# AQS.net
KiCad netlist of a schematic drawn in EAGLE
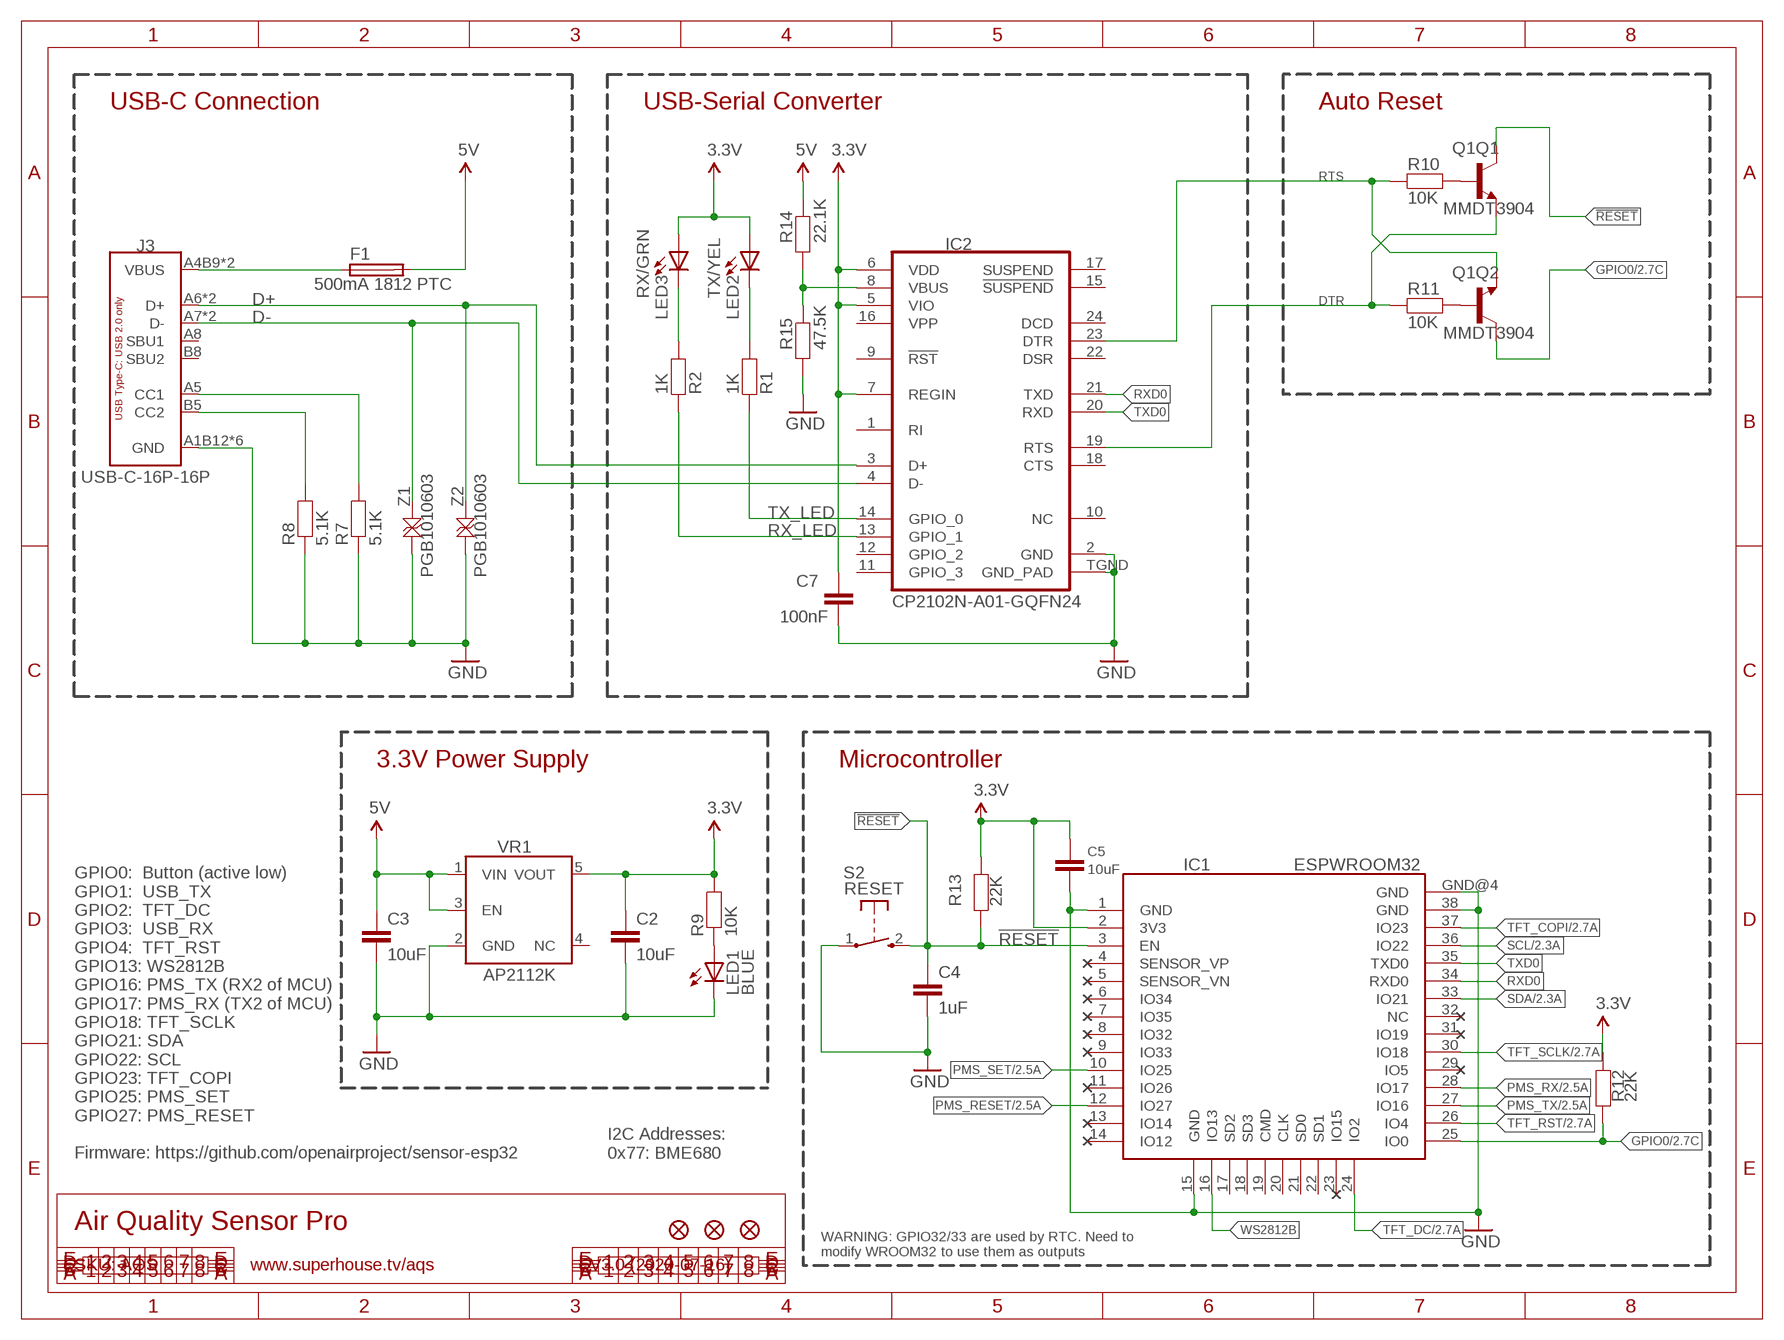
[diagram p0: schematic, sheet 1]
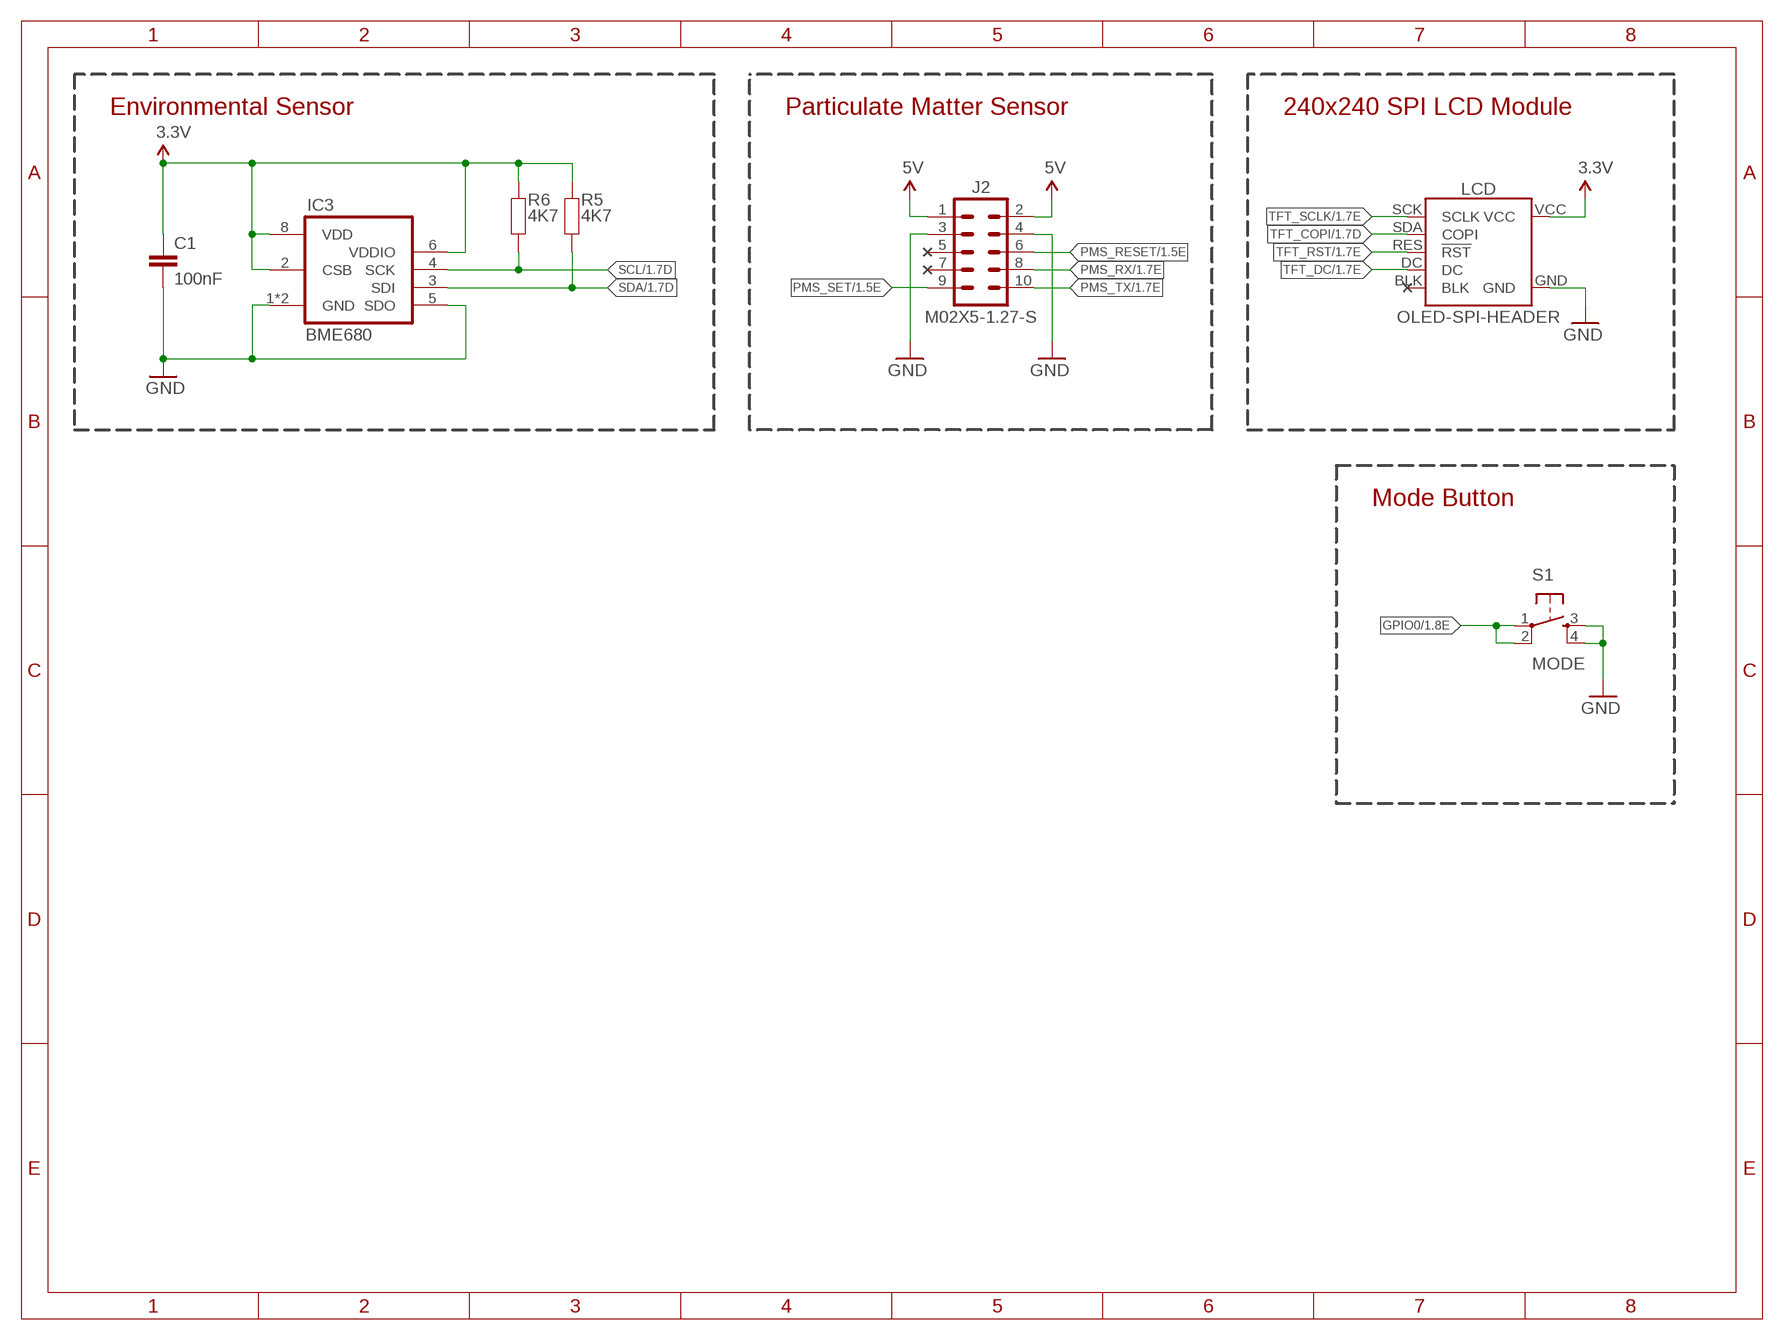
[diagram p1: schematic, sheet 2]

(export (version "E")
  (design (tool "Eeschema 10.0.6"))
  (components
    (comp (ref "C2")
      (value "10uF")
      (footprint "eagle-import:C0805")
      (libsource (lib "eagle-import") (part "CAP0805"))
    )
    (comp (ref "C3")
      (value "10uF")
      (footprint "eagle-import:C0805")
      (libsource (lib "eagle-import") (part "CAP0805"))
    )
    (comp (ref "C4")
      (value "1uF")
      (footprint "eagle-import:C0603")
      (libsource (lib "eagle-import") (part "CAP0603"))
    )
    (comp (ref "C5")
      (value "10uF")
      (footprint "eagle-import:C0805")
      (libsource (lib "eagle-import") (part "CAP0805"))
    )
    (comp (ref "C7")
      (value "100nF")
      (footprint "eagle-import:C0603")
      (libsource (lib "eagle-import") (part "CAP0603"))
    )
    (comp (ref "F1")
      (value "500mA 1812 PTC")
      (footprint "eagle-import:1812")
      (libsource (lib "eagle-import") (part "PTC050"))
    )
    (comp (ref "IC1")
      (value "ESPWROOM32")
      (footprint "eagle-import:ESPWROOM32")
      (libsource (lib "eagle-import") (part "ESPWROOM32"))
    )
    (comp (ref "IC2")
      (value "CP2102N-A01-GQFN24")
      (footprint "eagle-import:QFN-24")
      (libsource (lib "eagle-import") (part "CP2104"))
    )
    (comp (ref "J3")
      (value "USB-C-16P-16P")
      (footprint "eagle-import:USB-C-16P")
      (libsource (lib "eagle-import") (part "USB-C-16P-16P"))
    )
    (comp (ref "LED1")
      (value "BLUE")
      (footprint "eagle-import:LED-0603")
      (libsource (lib "eagle-import") (part "LED0603"))
    )
    (comp (ref "LED2")
      (value "TX/YEL")
      (footprint "eagle-import:LED-0603")
      (libsource (lib "eagle-import") (part "LED0603"))
    )
    (comp (ref "LED3")
      (value "RX/GRN")
      (footprint "eagle-import:LED-0603")
      (libsource (lib "eagle-import") (part "LED0603"))
    )
    (comp (ref "Q1")
      (value "MMDT3904")
      (footprint "eagle-import:SOT-363")
      (libsource (lib "eagle-import") (part "TRANS_NPN_DUAL-MMDT3904"))
    )
    (comp (ref "R1")
      (value "1K")
      (footprint "eagle-import:R0603")
      (libsource (lib "eagle-import") (part "RESISTOR0603"))
    )
    (comp (ref "R2")
      (value "1K")
      (footprint "eagle-import:R0603")
      (libsource (lib "eagle-import") (part "RESISTOR0603"))
    )
    (comp (ref "R7")
      (value "5.1K")
      (footprint "eagle-import:R0603")
      (libsource (lib "eagle-import") (part "RESISTOR0603"))
    )
    (comp (ref "R8")
      (value "5.1K")
      (footprint "eagle-import:R0603")
      (libsource (lib "eagle-import") (part "RESISTOR0603"))
    )
    (comp (ref "R9")
      (value "10K")
      (footprint "eagle-import:R0603")
      (libsource (lib "eagle-import") (part "RESISTOR0603"))
    )
    (comp (ref "R10")
      (value "10K")
      (footprint "eagle-import:R0603")
      (libsource (lib "eagle-import") (part "RESISTOR0603"))
    )
    (comp (ref "R11")
      (value "10K")
      (footprint "eagle-import:R0603")
      (libsource (lib "eagle-import") (part "RESISTOR0603"))
    )
    (comp (ref "R12")
      (value "22K")
      (footprint "eagle-import:R0603")
      (libsource (lib "eagle-import") (part "RESISTOR0603"))
    )
    (comp (ref "R13")
      (value "22K")
      (footprint "eagle-import:R0603")
      (libsource (lib "eagle-import") (part "RESISTOR0603"))
    )
    (comp (ref "R14")
      (value "22.1K")
      (footprint "eagle-import:R0603")
      (libsource (lib "eagle-import") (part "RESISTOR0603"))
    )
    (comp (ref "R15")
      (value "47.5K")
      (footprint "eagle-import:R0603")
      (libsource (lib "eagle-import") (part "RESISTOR0603"))
    )
    (comp (ref "S2")
      (value "RESET")
      (footprint "eagle-import:TACTILE_SMT_3X4X2")
      (libsource (lib "eagle-import") (part "TAC_SWITCH_2PINSMT"))
    )
    (comp (ref "U$23")
      (value "FIDUCIAL1X2")
      (footprint "eagle-import:FIDUCIAL-1X2")
      (libsource (lib "eagle-import") (part "FIDUCIAL1X2"))
    )
    (comp (ref "U$24")
      (value "FIDUCIAL1X2")
      (footprint "eagle-import:FIDUCIAL-1X2")
      (libsource (lib "eagle-import") (part "FIDUCIAL1X2"))
    )
    (comp (ref "U$25")
      (value "FIDUCIAL1X2")
      (footprint "eagle-import:FIDUCIAL-1X2")
      (libsource (lib "eagle-import") (part "FIDUCIAL1X2"))
    )
    (comp (ref "VR1")
      (value "AP2112KSOT25")
      (footprint "eagle-import:SOT23-5")
      (libsource (lib "eagle-import") (part "AP2112KSOT25"))
    )
    (comp (ref "Z1")
      (value "PGB1010603")
      (footprint "eagle-import:TVS0603")
      (libsource (lib "eagle-import") (part "TVS0603"))
    )
    (comp (ref "Z2")
      (value "PGB1010603")
      (footprint "eagle-import:TVS0603")
      (libsource (lib "eagle-import") (part "TVS0603"))
    )
    (comp (ref "C1")
      (value "100nF")
      (footprint "eagle-import:C0603")
      (libsource (lib "eagle-import") (part "CAP0603"))
    )
    (comp (ref "IC3")
      (value "BME680")
      (footprint "eagle-import:BME680")
      (libsource (lib "eagle-import") (part "BME680"))
    )
    (comp (ref "J2")
      (value "M02X5-1.27-S")
      (footprint "eagle-import:2X05-1.27-S")
      (libsource (lib "eagle-import") (part "M02X5-1.27-S"))
    )
    (comp (ref "LCD")
      (value "OLED-SPI-HEADER")
      (footprint "eagle-import:OLED-240X240-1.3-HEADER")
      (libsource (lib "eagle-import") (part "OLED-SPI-HEADER"))
    )
    (comp (ref "R5")
      (value "4K7")
      (footprint "eagle-import:R0603")
      (libsource (lib "eagle-import") (part "RESISTOR0603"))
    )
    (comp (ref "R6")
      (value "4K7")
      (footprint "eagle-import:R0603")
      (libsource (lib "eagle-import") (part "RESISTOR0603"))
    )
    (comp (ref "S1")
      (value "MODE")
      (footprint "eagle-import:TACTILE-PTH-4.5MM")
      (libsource (lib "eagle-import") (part "TAC_SWITCH-PTH-4.5"))
    )
  )
  (nets
    (net (code "1") (name "3.3V") (class "Default")
      (node (ref "C1") (pin "1") (pinfunction "1_1") (pintype "passive"))
      (node (ref "C2") (pin "1") (pinfunction "1_1") (pintype "passive"))
      (node (ref "C5") (pin "1") (pinfunction "1_1") (pintype "passive"))
      (node (ref "C7") (pin "1") (pinfunction "1_1") (pintype "passive"))
      (node (ref "IC1") (pin "2") (pinfunction "3V3_2") (pintype "power_in"))
      (node (ref "IC2") (pin "5") (pinfunction "VIO_5") (pintype "bidirectional"))
      (node (ref "IC2") (pin "6") (pinfunction "VDD_6") (pintype "power_in"))
      (node (ref "IC2") (pin "7") (pinfunction "REGIN_7") (pintype "power_in"))
      (node (ref "IC3") (pin "2") (pinfunction "CSB_2") (pintype "input"))
      (node (ref "IC3") (pin "6") (pinfunction "VDDIO_6") (pintype "power_in"))
      (node (ref "IC3") (pin "8") (pinfunction "VDD_8") (pintype "power_in"))
      (node (ref "LCD") (pin "VCC") (pinfunction "VCC_VCC") (pintype "bidirectional"))
      (node (ref "LED2") (pin "A") (pinfunction "A_A") (pintype "passive"))
      (node (ref "LED3") (pin "A") (pinfunction "A_A") (pintype "passive"))
      (node (ref "R12") (pin "1") (pinfunction "1_1") (pintype "passive"))
      (node (ref "R13") (pin "1") (pinfunction "1_1") (pintype "passive"))
      (node (ref "R5") (pin "2") (pinfunction "2_2") (pintype "passive"))
      (node (ref "R6") (pin "2") (pinfunction "2_2") (pintype "passive"))
      (node (ref "R9") (pin "2") (pinfunction "2_2") (pintype "passive"))
      (node (ref "VR1") (pin "5") (pinfunction "VOUT_5") (pintype "bidirectional"))
    )
    (net (code "2") (name "5V") (class "Default")
      (node (ref "C3") (pin "1") (pinfunction "1_1") (pintype "passive"))
      (node (ref "F1") (pin "2") (pinfunction "2_2") (pintype "passive"))
      (node (ref "J2") (pin "1") (pinfunction "1_1") (pintype "passive"))
      (node (ref "J2") (pin "2") (pinfunction "2_2") (pintype "passive"))
      (node (ref "R14") (pin "2") (pinfunction "2_2") (pintype "passive"))
      (node (ref "VR1") (pin "1") (pinfunction "VIN_1") (pintype "bidirectional"))
      (node (ref "VR1") (pin "3") (pinfunction "EN_3") (pintype "bidirectional"))
    )
    (net (code "3") (name "D+") (class "Default")
      (node (ref "IC2") (pin "3") (pinfunction "D+_3") (pintype "bidirectional"))
      (node (ref "J3") (pin "A6") (pinfunction "D+_A6") (pintype "bidirectional"))
      (node (ref "J3") (pin "B6") (pinfunction "D+_B6") (pintype "bidirectional"))
      (node (ref "Z2") (pin "2") (pinfunction "2_2") (pintype "passive"))
    )
    (net (code "4") (name "D-") (class "Default")
      (node (ref "IC2") (pin "4") (pinfunction "D-_4") (pintype "bidirectional"))
      (node (ref "J3") (pin "A7") (pinfunction "D-_A7") (pintype "bidirectional"))
      (node (ref "J3") (pin "B7") (pinfunction "D-_B7") (pintype "bidirectional"))
      (node (ref "Z1") (pin "2") (pinfunction "2_2") (pintype "passive"))
    )
    (net (code "5") (name "DTR") (class "Default")
      (node (ref "IC2") (pin "23") (pinfunction "DTR_23") (pintype "output"))
      (node (ref "Q1") (pin "1") (pinfunction "E_1") (pintype "passive"))
      (node (ref "R10") (pin "1") (pinfunction "1_1") (pintype "passive"))
    )
    (net (code "6") (name "GND") (class "Default")
      (node (ref "C1") (pin "2") (pinfunction "2_2") (pintype "passive"))
      (node (ref "C2") (pin "2") (pinfunction "2_2") (pintype "passive"))
      (node (ref "C3") (pin "2") (pinfunction "2_2") (pintype "passive"))
      (node (ref "C4") (pin "2") (pinfunction "2_2") (pintype "passive"))
      (node (ref "C5") (pin "2") (pinfunction "2_2") (pintype "passive"))
      (node (ref "C7") (pin "2") (pinfunction "2_2") (pintype "passive"))
      (node (ref "IC1") (pin "1") (pinfunction "GND_1") (pintype "power_in"))
      (node (ref "IC1") (pin "15") (pinfunction "GND_15") (pintype "power_in"))
      (node (ref "IC1") (pin "38") (pinfunction "GND_38") (pintype "power_in"))
      (node (ref "IC1") (pin "GND@4") (pinfunction "GND_GND@4") (pintype "power_in"))
      (node (ref "IC2") (pin "2") (pinfunction "GND_2") (pintype "power_in"))
      (node (ref "IC2") (pin "TGND") (pinfunction "GND_PAD_TGND") (pintype "power_in"))
      (node (ref "IC3") (pin "1") (pinfunction "GND_1") (pintype "power_in"))
      (node (ref "IC3") (pin "5") (pinfunction "SDO_5") (pintype "input"))
      (node (ref "IC3") (pin "7") (pinfunction "GND_7") (pintype "power_in"))
      (node (ref "J2") (pin "3") (pinfunction "3_3") (pintype "passive"))
      (node (ref "J2") (pin "4") (pinfunction "4_4") (pintype "passive"))
      (node (ref "J3") (pin "A12B1") (pinfunction "GND_A12B1") (pintype "power_in"))
      (node (ref "J3") (pin "A1B12") (pinfunction "GND_A1B12") (pintype "power_in"))
      (node (ref "J3") (pin "FIX1") (pinfunction "GND_FIX1") (pintype "power_in"))
      (node (ref "J3") (pin "FIX2") (pinfunction "GND_FIX2") (pintype "power_in"))
      (node (ref "J3") (pin "FIX3") (pinfunction "GND_FIX3") (pintype "power_in"))
      (node (ref "J3") (pin "FIX4") (pinfunction "GND_FIX4") (pintype "power_in"))
      (node (ref "LCD") (pin "GND") (pinfunction "GND_GND") (pintype "bidirectional"))
      (node (ref "LED1") (pin "C") (pinfunction "C_C") (pintype "passive"))
      (node (ref "R15") (pin "1") (pinfunction "1_1") (pintype "passive"))
      (node (ref "R7") (pin "1") (pinfunction "1_1") (pintype "passive"))
      (node (ref "R8") (pin "1") (pinfunction "1_1") (pintype "passive"))
      (node (ref "S1") (pin "3") (pinfunction "3_3") (pintype "passive"))
      (node (ref "S1") (pin "4") (pinfunction "4_4") (pintype "passive"))
      (node (ref "S2") (pin "1") (pinfunction "P_1") (pintype "passive"))
      (node (ref "VR1") (pin "2") (pinfunction "GND_2") (pintype "bidirectional"))
      (node (ref "Z1") (pin "1") (pinfunction "1_1") (pintype "passive"))
      (node (ref "Z2") (pin "1") (pinfunction "1_1") (pintype "passive"))
    )
    (net (code "7") (name "GPIO0") (class "Default")
      (node (ref "IC1") (pin "25") (pinfunction "IO0_25") (pintype "bidirectional"))
      (node (ref "Q1") (pin "6") (pinfunction "C_6") (pintype "passive"))
      (node (ref "R12") (pin "2") (pinfunction "2_2") (pintype "passive"))
      (node (ref "S1") (pin "1") (pinfunction "1_1") (pintype "passive"))
      (node (ref "S1") (pin "2") (pinfunction "2_2") (pintype "passive"))
    )
    (net (code "8") (name "Net-(F1-Pad1)") (class "Default")
      (node (ref "F1") (pin "1") (pinfunction "1_1") (pintype "passive"))
      (node (ref "J3") (pin "A4B9") (pinfunction "VBUS_A4B9") (pintype "power_in"))
      (node (ref "J3") (pin "A9B4") (pinfunction "VBUS_A9B4") (pintype "power_in"))
    )
    (net (code "9") (name "Net-(IC2-VBUS)") (class "Default")
      (node (ref "IC2") (pin "8") (pinfunction "VBUS_8") (pintype "bidirectional"))
      (node (ref "R14") (pin "1") (pinfunction "1_1") (pintype "passive"))
      (node (ref "R15") (pin "2") (pinfunction "2_2") (pintype "passive"))
    )
    (net (code "10") (name "Net-(J3-CC1)") (class "Default")
      (node (ref "J3") (pin "A5") (pinfunction "CC1_A5") (pintype "bidirectional"))
      (node (ref "R7") (pin "2") (pinfunction "2_2") (pintype "passive"))
    )
    (net (code "11") (name "Net-(J3-CC2)") (class "Default")
      (node (ref "J3") (pin "B5") (pinfunction "CC2_B5") (pintype "bidirectional"))
      (node (ref "R8") (pin "2") (pinfunction "2_2") (pintype "passive"))
    )
    (net (code "12") (name "Net-(LED1-PadA)") (class "Default")
      (node (ref "LED1") (pin "A") (pinfunction "A_A") (pintype "passive"))
      (node (ref "R9") (pin "1") (pinfunction "1_1") (pintype "passive"))
    )
    (net (code "13") (name "Net-(LED2-PadC)") (class "Default")
      (node (ref "LED2") (pin "C") (pinfunction "C_C") (pintype "passive"))
      (node (ref "R1") (pin "2") (pinfunction "2_2") (pintype "passive"))
    )
    (net (code "14") (name "Net-(LED3-PadC)") (class "Default")
      (node (ref "LED3") (pin "C") (pinfunction "C_C") (pintype "passive"))
      (node (ref "R2") (pin "2") (pinfunction "2_2") (pintype "passive"))
    )
    (net (code "15") (name "Net-(Q1A-B)") (class "Default")
      (node (ref "Q1") (pin "5") (pinfunction "B_5") (pintype "passive"))
      (node (ref "R10") (pin "2") (pinfunction "2_2") (pintype "passive"))
    )
    (net (code "16") (name "Net-(Q1B-B)") (class "Default")
      (node (ref "Q1") (pin "2") (pinfunction "B_2") (pintype "passive"))
      (node (ref "R11") (pin "2") (pinfunction "2_2") (pintype "passive"))
    )
    (net (code "17") (name "PMS_RESET") (class "Default")
      (node (ref "IC1") (pin "12") (pinfunction "IO27_12") (pintype "bidirectional"))
      (node (ref "J2") (pin "6") (pinfunction "6_6") (pintype "passive"))
    )
    (net (code "18") (name "PMS_RX") (class "Default")
      (node (ref "IC1") (pin "28") (pinfunction "IO17_28") (pintype "bidirectional"))
      (node (ref "J2") (pin "8") (pinfunction "8_8") (pintype "passive"))
    )
    (net (code "19") (name "PMS_SET") (class "Default")
      (node (ref "IC1") (pin "10") (pinfunction "IO25_10") (pintype "bidirectional"))
      (node (ref "J2") (pin "9") (pinfunction "9_9") (pintype "passive"))
    )
    (net (code "20") (name "PMS_TX") (class "Default")
      (node (ref "IC1") (pin "27") (pinfunction "IO16_27") (pintype "bidirectional"))
      (node (ref "J2") (pin "10") (pinfunction "10_10") (pintype "passive"))
    )
    (net (code "21") (name "RTS") (class "Default")
      (node (ref "IC2") (pin "19") (pinfunction "RTS_19") (pintype "output"))
      (node (ref "Q1") (pin "4") (pinfunction "E_4") (pintype "passive"))
      (node (ref "R11") (pin "1") (pinfunction "1_1") (pintype "passive"))
    )
    (net (code "22") (name "RXD0") (class "Default")
      (node (ref "IC1") (pin "34") (pinfunction "RXD0_34") (pintype "bidirectional"))
      (node (ref "IC2") (pin "21") (pinfunction "TXD_21") (pintype "output"))
    )
    (net (code "23") (name "RX_LED") (class "Default")
      (node (ref "IC2") (pin "13") (pinfunction "GPIO_1_13") (pintype "bidirectional"))
      (node (ref "R2") (pin "1") (pinfunction "1_1") (pintype "passive"))
    )
    (net (code "24") (name "SCL") (class "Default")
      (node (ref "IC1") (pin "36") (pinfunction "IO22_36") (pintype "bidirectional"))
      (node (ref "IC3") (pin "4") (pinfunction "SCK_4") (pintype "bidirectional"))
      (node (ref "R6") (pin "1") (pinfunction "1_1") (pintype "passive"))
    )
    (net (code "25") (name "SDA") (class "Default")
      (node (ref "IC1") (pin "33") (pinfunction "IO21_33") (pintype "bidirectional"))
      (node (ref "IC3") (pin "3") (pinfunction "SDI_3") (pintype "bidirectional"))
      (node (ref "R5") (pin "1") (pinfunction "1_1") (pintype "passive"))
    )
    (net (code "26") (name "TFT_COPI") (class "Default")
      (node (ref "IC1") (pin "37") (pinfunction "IO23_37") (pintype "bidirectional"))
      (node (ref "LCD") (pin "SDA") (pinfunction "COPI_SDA") (pintype "bidirectional"))
    )
    (net (code "27") (name "TFT_DC") (class "Default")
      (node (ref "IC1") (pin "24") (pinfunction "IO2_24") (pintype "bidirectional"))
      (node (ref "LCD") (pin "DC") (pinfunction "DC_DC") (pintype "bidirectional"))
    )
    (net (code "28") (name "TFT_RST") (class "Default")
      (node (ref "IC1") (pin "26") (pinfunction "IO4_26") (pintype "bidirectional"))
      (node (ref "LCD") (pin "RES") (pinfunction "~{RST}_RES") (pintype "bidirectional"))
    )
    (net (code "29") (name "TFT_SCLK") (class "Default")
      (node (ref "IC1") (pin "30") (pinfunction "IO18_30") (pintype "bidirectional"))
      (node (ref "LCD") (pin "SCK") (pinfunction "SCLK_SCK") (pintype "bidirectional"))
    )
    (net (code "30") (name "TXD0") (class "Default")
      (node (ref "IC1") (pin "35") (pinfunction "TXD0_35") (pintype "bidirectional"))
      (node (ref "IC2") (pin "20") (pinfunction "RXD_20") (pintype "input"))
    )
    (net (code "31") (name "TX_LED") (class "Default")
      (node (ref "IC2") (pin "14") (pinfunction "GPIO_0_14") (pintype "bidirectional"))
      (node (ref "R1") (pin "1") (pinfunction "1_1") (pintype "passive"))
    )
    (net (code "32") (name "WS2812B") (class "Default")
      (node (ref "IC1") (pin "16") (pinfunction "IO13_16") (pintype "bidirectional"))
    )
    (net (code "33") (name "unconnected-(IC1-CLK-Pad20)") (class "Default")
      (node (ref "IC1") (pin "20") (pinfunction "CLK_20") (pintype "bidirectional"))
    )
    (net (code "34") (name "unconnected-(IC1-CMD-Pad19)") (class "Default")
      (node (ref "IC1") (pin "19") (pinfunction "CMD_19") (pintype "bidirectional"))
    )
    (net (code "35") (name "unconnected-(IC1-IO5-Pad29)") (class "Default")
      (node (ref "IC1") (pin "29") (pinfunction "IO5_29") (pintype "bidirectional"))
    )
    (net (code "36") (name "unconnected-(IC1-IO12-Pad14)") (class "Default")
      (node (ref "IC1") (pin "14") (pinfunction "IO12_14") (pintype "bidirectional"))
    )
    (net (code "37") (name "unconnected-(IC1-IO14-Pad13)") (class "Default")
      (node (ref "IC1") (pin "13") (pinfunction "IO14_13") (pintype "bidirectional"))
    )
    (net (code "38") (name "unconnected-(IC1-IO15-Pad23)") (class "Default")
      (node (ref "IC1") (pin "23") (pinfunction "IO15_23") (pintype "bidirectional"))
    )
    (net (code "39") (name "unconnected-(IC1-IO19-Pad31)") (class "Default")
      (node (ref "IC1") (pin "31") (pinfunction "IO19_31") (pintype "bidirectional"))
    )
    (net (code "40") (name "unconnected-(IC1-IO26-Pad11)") (class "Default")
      (node (ref "IC1") (pin "11") (pinfunction "IO26_11") (pintype "bidirectional"))
    )
    (net (code "41") (name "unconnected-(IC1-IO32-Pad8)") (class "Default")
      (node (ref "IC1") (pin "8") (pinfunction "IO32_8") (pintype "bidirectional"))
    )
    (net (code "42") (name "unconnected-(IC1-IO33-Pad9)") (class "Default")
      (node (ref "IC1") (pin "9") (pinfunction "IO33_9") (pintype "bidirectional"))
    )
    (net (code "43") (name "unconnected-(IC1-IO34-Pad6)") (class "Default")
      (node (ref "IC1") (pin "6") (pinfunction "IO34_6") (pintype "bidirectional"))
    )
    (net (code "44") (name "unconnected-(IC1-IO35-Pad7)") (class "Default")
      (node (ref "IC1") (pin "7") (pinfunction "IO35_7") (pintype "bidirectional"))
    )
    (net (code "45") (name "unconnected-(IC1-NC-Pad32)") (class "Default")
      (node (ref "IC1") (pin "32") (pinfunction "NC_32") (pintype "bidirectional"))
    )
    (net (code "46") (name "unconnected-(IC1-SD0-Pad21)") (class "Default")
      (node (ref "IC1") (pin "21") (pinfunction "SD0_21") (pintype "bidirectional"))
    )
    (net (code "47") (name "unconnected-(IC1-SD1-Pad22)") (class "Default")
      (node (ref "IC1") (pin "22") (pinfunction "SD1_22") (pintype "bidirectional"))
    )
    (net (code "48") (name "unconnected-(IC1-SD2-Pad17)") (class "Default")
      (node (ref "IC1") (pin "17") (pinfunction "SD2_17") (pintype "bidirectional"))
    )
    (net (code "49") (name "unconnected-(IC1-SD3-Pad18)") (class "Default")
      (node (ref "IC1") (pin "18") (pinfunction "SD3_18") (pintype "bidirectional"))
    )
    (net (code "50") (name "unconnected-(IC1-SENSOR_VN-Pad5)") (class "Default")
      (node (ref "IC1") (pin "5") (pinfunction "SENSOR_VN_5") (pintype "bidirectional"))
    )
    (net (code "51") (name "unconnected-(IC1-SENSOR_VP-Pad4)") (class "Default")
      (node (ref "IC1") (pin "4") (pinfunction "SENSOR_VP_4") (pintype "bidirectional"))
    )
    (net (code "52") (name "unconnected-(IC2-CTS-Pad18)") (class "Default")
      (node (ref "IC2") (pin "18") (pinfunction "CTS_18") (pintype "input"))
    )
    (net (code "53") (name "unconnected-(IC2-DCD-Pad24)") (class "Default")
      (node (ref "IC2") (pin "24") (pinfunction "DCD_24") (pintype "input"))
    )
    (net (code "54") (name "unconnected-(IC2-DSR-Pad22)") (class "Default")
      (node (ref "IC2") (pin "22") (pinfunction "DSR_22") (pintype "input"))
    )
    (net (code "55") (name "unconnected-(IC2-GPIO_2-Pad12)") (class "Default")
      (node (ref "IC2") (pin "12") (pinfunction "GPIO_2_12") (pintype "bidirectional"))
    )
    (net (code "56") (name "unconnected-(IC2-GPIO_3-Pad11)") (class "Default")
      (node (ref "IC2") (pin "11") (pinfunction "GPIO_3_11") (pintype "bidirectional"))
    )
    (net (code "57") (name "unconnected-(IC2-NC-Pad10)") (class "Default")
      (node (ref "IC2") (pin "10") (pinfunction "NC_10") (pintype "input"))
    )
    (net (code "58") (name "unconnected-(IC2-RI-Pad1)") (class "Default")
      (node (ref "IC2") (pin "1") (pinfunction "RI_1") (pintype "input"))
    )
    (net (code "59") (name "unconnected-(IC2-SUSPEND-Pad17)") (class "Default")
      (node (ref "IC2") (pin "17") (pinfunction "SUSPEND_17") (pintype "output"))
    )
    (net (code "60") (name "unconnected-(IC2-VPP-Pad16)") (class "Default")
      (node (ref "IC2") (pin "16") (pinfunction "VPP_16") (pintype "bidirectional"))
    )
    (net (code "61") (name "unconnected-(IC2-~{RST}-Pad9)") (class "Default")
      (node (ref "IC2") (pin "9") (pinfunction "~{RST}_9") (pintype "bidirectional"))
    )
    (net (code "62") (name "unconnected-(IC2-~{SUSPEND}-Pad15)") (class "Default")
      (node (ref "IC2") (pin "15") (pinfunction "~{SUSPEND}_15") (pintype "output"))
    )
    (net (code "63") (name "unconnected-(J2-Pad5)") (class "Default")
      (node (ref "J2") (pin "5") (pinfunction "5_5") (pintype "passive"))
    )
    (net (code "64") (name "unconnected-(J2-Pad7)") (class "Default")
      (node (ref "J2") (pin "7") (pinfunction "7_7") (pintype "passive"))
    )
    (net (code "65") (name "unconnected-(J3-SBU1-PadA8)") (class "Default")
      (node (ref "J3") (pin "A8") (pinfunction "SBU1_A8") (pintype "bidirectional"))
    )
    (net (code "66") (name "unconnected-(J3-SBU2-PadB8)") (class "Default")
      (node (ref "J3") (pin "B8") (pinfunction "SBU2_B8") (pintype "bidirectional"))
    )
    (net (code "67") (name "unconnected-(LCD-PadBLK)") (class "Default")
      (node (ref "LCD") (pin "BLK") (pinfunction "BLK_BLK") (pintype "bidirectional"))
    )
    (net (code "68") (name "unconnected-(VR1-NC-Pad4)") (class "Default")
      (node (ref "VR1") (pin "4") (pinfunction "NC_4") (pintype "bidirectional"))
    )
    (net (code "69") (name "~{RESET}") (class "Default")
      (node (ref "C4") (pin "1") (pinfunction "1_1") (pintype "passive"))
      (node (ref "IC1") (pin "3") (pinfunction "EN_3") (pintype "bidirectional"))
      (node (ref "Q1") (pin "3") (pinfunction "C_3") (pintype "passive"))
      (node (ref "R13") (pin "2") (pinfunction "2_2") (pintype "passive"))
      (node (ref "S2") (pin "2") (pinfunction "S_2") (pintype "passive"))
    )
  )
)
